# gpi-bottom.net
KiCad netlist of a schematic drawn in EAGLE
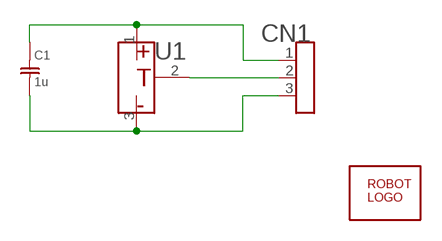
[diagram p0: schematic, sheet 1]

(export (version "E")
  (design (tool "Eeschema 10.0.6"))
  (components
    (comp (ref "C1")
      (value "1u")
      (footprint "eagle-import:SMD0603")
      (libsource (lib "eagle-import") (part "C0603"))
    )
    (comp (ref "CN1")
      (value "HEADER-3X12MM")
      (footprint "eagle-import:HEADER-3X1-2SMD")
      (libsource (lib "eagle-import") (part "HEADER-3X12MM"))
    )
    (comp (ref "U$1")
      (value "ROBOTMAN-LOGO")
      (footprint "eagle-import:ROBOTMAN-LOGO")
      (libsource (lib "eagle-import") (part "ROBOTMAN-LOGO"))
    )
    (comp (ref "U1")
      (value "TEMPERATURE")
      (footprint "eagle-import:SOT-23")
      (libsource (lib "eagle-import") (part "TEMPERATURE"))
    )
  )
  (nets
    (net (code "1") (name "Net-(C1-P$1)") (class "Default")
      (node (ref "C1") (pin "1") (pinfunction "P$1_1") (pintype "passive"))
      (node (ref "CN1") (pin "1") (pinfunction "1_1") (pintype "bidirectional"))
      (node (ref "U1") (pin "1") (pinfunction "V_1") (pintype "bidirectional"))
    )
    (net (code "2") (name "Net-(C1-P$2)") (class "Default")
      (node (ref "C1") (pin "2") (pinfunction "P$2_2") (pintype "passive"))
      (node (ref "CN1") (pin "3") (pinfunction "3_3") (pintype "bidirectional"))
      (node (ref "U1") (pin "3") (pinfunction "G_3") (pintype "bidirectional"))
    )
    (net (code "3") (name "Net-(U1-OUT)") (class "Default")
      (node (ref "CN1") (pin "2") (pinfunction "2_2") (pintype "bidirectional"))
      (node (ref "U1") (pin "2") (pinfunction "OUT_2") (pintype "bidirectional"))
    )
  )
)
